# Cerebro.net
KiCad netlist of a schematic drawn in Altium Designer
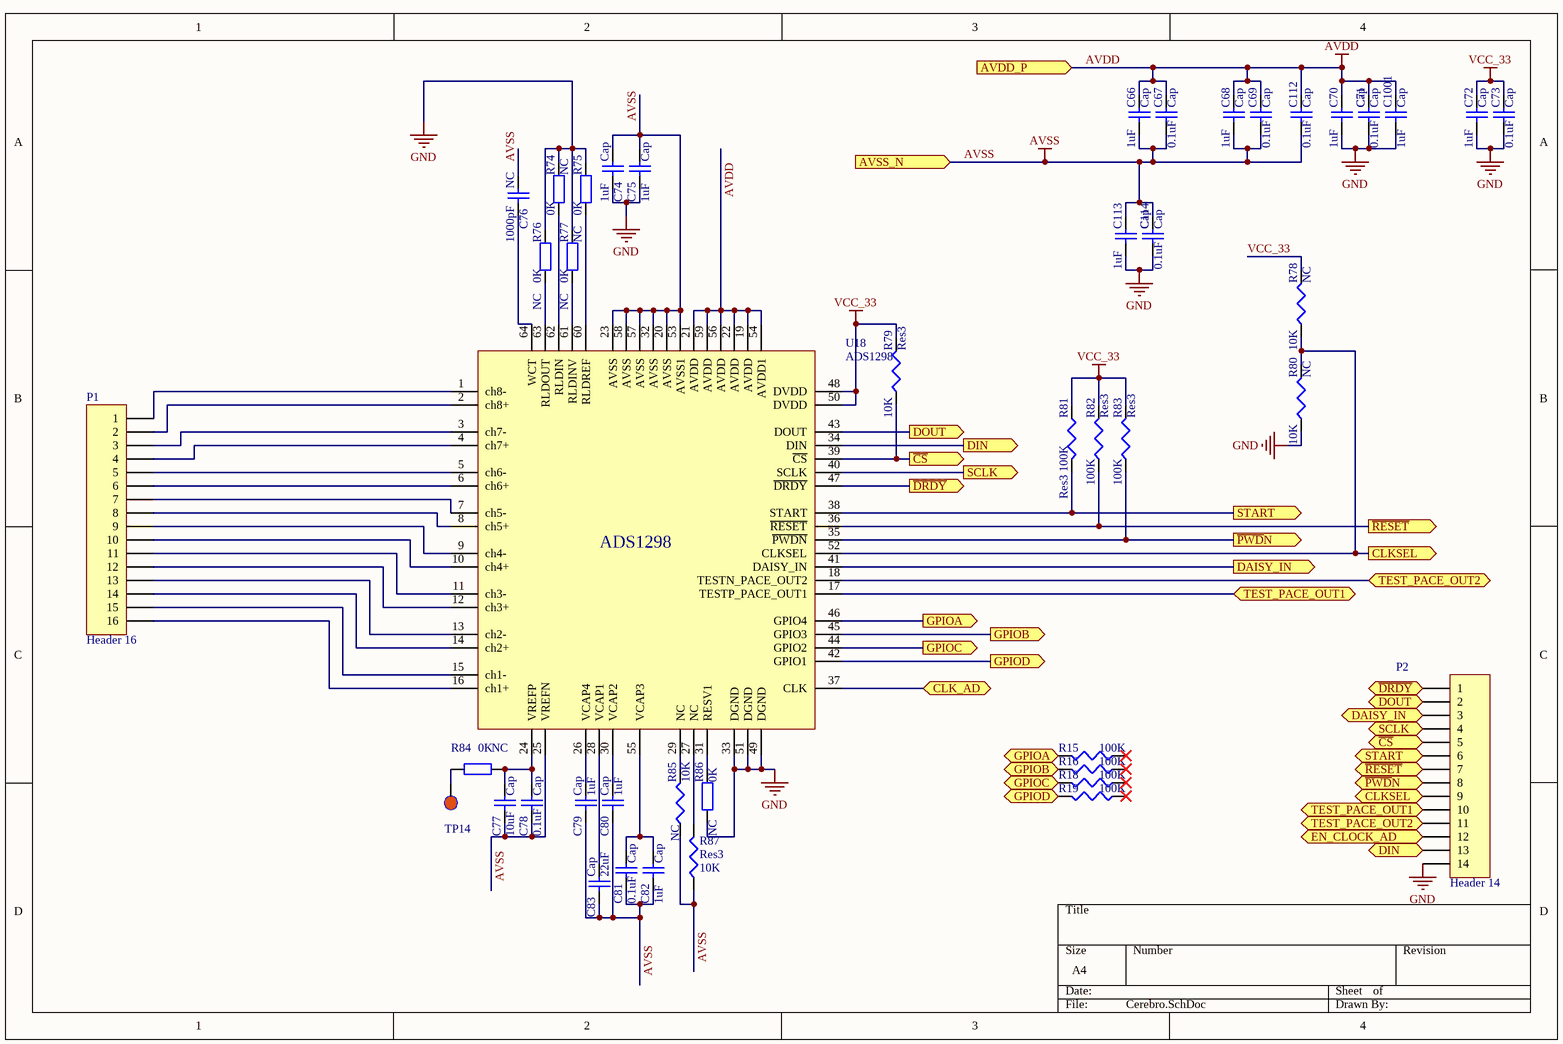
[diagram p0: Cerebro.SchDoc]

(export (version "E")
  (design (tool "Eeschema 10.0.6"))
  (components
    (comp (ref "C66")
      (value "Cap")
      (footprint "cap_0402_R - modified")
      (description "Capacitor")
      (fields (field (name "ALTIUM_VALUE") "1uF") (field (name "PUBLISHER") "Altium Limited"))
      (libsource (lib "Miscellaneous Devices") (part "Cap"))
    )
    (comp (ref "C67")
      (value "Cap")
      (footprint "cap_0402_R - modified")
      (description "Capacitor")
      (fields (field (name "ALTIUM_VALUE") "0.1uF") (field (name "PUBLISHER") "Altium Limited"))
      (libsource (lib "Miscellaneous Devices") (part "Cap"))
    )
    (comp (ref "C68")
      (value "Cap")
      (footprint "cap_0402_R - modified")
      (description "Capacitor")
      (fields (field (name "ALTIUM_VALUE") "1uF") (field (name "PUBLISHER") "Altium Limited"))
      (libsource (lib "Miscellaneous Devices") (part "Cap"))
    )
    (comp (ref "C69")
      (value "Cap")
      (footprint "cap_0402_R - modified")
      (description "Capacitor")
      (fields (field (name "ALTIUM_VALUE") "0.1uF") (field (name "PUBLISHER") "Altium Limited"))
      (libsource (lib "Miscellaneous Devices") (part "Cap"))
    )
    (comp (ref "C70")
      (value "Cap")
      (footprint "cap_0402_R - modified")
      (description "Capacitor")
      (fields (field (name "ALTIUM_VALUE") "1uF") (field (name "PUBLISHER") "Altium Limited"))
      (libsource (lib "Miscellaneous Devices") (part "Cap"))
    )
    (comp (ref "C71")
      (value "Cap")
      (footprint "cap_0402_R - modified")
      (description "Capacitor")
      (fields (field (name "ALTIUM_VALUE") "0.1uF") (field (name "PUBLISHER") "Altium Limited"))
      (libsource (lib "Miscellaneous Devices") (part "Cap"))
    )
    (comp (ref "C72")
      (value "Cap")
      (footprint "cap_0402_R - modified")
      (description "Capacitor")
      (fields (field (name "ALTIUM_VALUE") "1uF") (field (name "PUBLISHER") "Altium Limited"))
      (libsource (lib "Miscellaneous Devices") (part "Cap"))
    )
    (comp (ref "C73")
      (value "Cap")
      (footprint "cap_0402_R - modified")
      (description "Capacitor")
      (fields (field (name "ALTIUM_VALUE") "0.1uF") (field (name "PUBLISHER") "Altium Limited"))
      (libsource (lib "Miscellaneous Devices") (part "Cap"))
    )
    (comp (ref "C74")
      (value "Cap")
      (footprint "cap_0402_R - modified")
      (description "Capacitor")
      (fields (field (name "ALTIUM_VALUE") "1uF") (field (name "PUBLISHER") "Altium Limited"))
      (libsource (lib "Miscellaneous Devices") (part "Cap"))
    )
    (comp (ref "C75")
      (value "Cap")
      (footprint "cap_0402_R - modified")
      (description "Capacitor")
      (fields (field (name "ALTIUM_VALUE") "1uF") (field (name "PUBLISHER") "Altium Limited"))
      (libsource (lib "Miscellaneous Devices") (part "Cap"))
    )
    (comp (ref "C76")
      (value "NC")
      (footprint "cap_0402_R - modified")
      (description "Capacitor")
      (fields (field (name "ALTIUM_VALUE") "1000pF") (field (name "PUBLISHER") "Altium Limited"))
      (libsource (lib "Miscellaneous Devices") (part "Cap"))
    )
    (comp (ref "C77")
      (value "Cap")
      (footprint "cap_0402_R - modified")
      (description "Capacitor")
      (fields (field (name "ALTIUM_VALUE") "10uF") (field (name "PUBLISHER") "Altium Limited"))
      (libsource (lib "Miscellaneous Devices") (part "Cap"))
    )
    (comp (ref "C78")
      (value "Cap")
      (footprint "cap_0402_R - modified")
      (description "Capacitor")
      (fields (field (name "ALTIUM_VALUE") "0.1uF") (field (name "PUBLISHER") "Altium Limited"))
      (libsource (lib "Miscellaneous Devices") (part "Cap"))
    )
    (comp (ref "C79")
      (value "Cap")
      (footprint "cap_0402_R - modified")
      (description "Capacitor")
      (fields (field (name "ALTIUM_VALUE") "1uF") (field (name "PUBLISHER") "Altium Limited"))
      (libsource (lib "Miscellaneous Devices") (part "Cap"))
    )
    (comp (ref "C80")
      (value "Cap")
      (footprint "cap_0402_R - modified")
      (description "Capacitor")
      (fields (field (name "ALTIUM_VALUE") "1uF") (field (name "PUBLISHER") "Altium Limited"))
      (libsource (lib "Miscellaneous Devices") (part "Cap"))
    )
    (comp (ref "C81")
      (value "Cap")
      (footprint "cap_0402_R - modified")
      (description "Capacitor")
      (fields (field (name "ALTIUM_VALUE") "0.1uF") (field (name "PUBLISHER") "Altium Limited"))
      (libsource (lib "Miscellaneous Devices") (part "Cap"))
    )
    (comp (ref "C82")
      (value "Cap")
      (footprint "cap_0402_R - modified")
      (description "Capacitor")
      (fields (field (name "ALTIUM_VALUE") "1uF") (field (name "PUBLISHER") "Altium Limited"))
      (libsource (lib "Miscellaneous Devices") (part "Cap"))
    )
    (comp (ref "C83")
      (value "Cap")
      (footprint "cap_0402_R - modified")
      (description "Capacitor")
      (fields (field (name "ALTIUM_VALUE") "22uF") (field (name "PUBLISHER") "Altium Limited"))
      (libsource (lib "Miscellaneous Devices") (part "Cap"))
    )
    (comp (ref "C112")
      (value "Cap")
      (footprint "cap_0402_R - modified")
      (description "Capacitor")
      (fields (field (name "ALTIUM_VALUE") "0.1uF") (field (name "PUBLISHER") "Altium Limited"))
      (libsource (lib "Miscellaneous Devices") (part "Cap"))
    )
    (comp (ref "C113")
      (value "Cap")
      (footprint "cap_0402_R - modified")
      (description "Capacitor")
      (fields (field (name "ALTIUM_VALUE") "1uF") (field (name "PUBLISHER") "Altium Limited"))
      (libsource (lib "Miscellaneous Devices") (part "Cap"))
    )
    (comp (ref "C114")
      (value "Cap")
      (footprint "cap_0402_R - modified")
      (description "Capacitor")
      (fields (field (name "ALTIUM_VALUE") "0.1uF") (field (name "PUBLISHER") "Altium Limited"))
      (libsource (lib "Miscellaneous Devices") (part "Cap"))
    )
    (comp (ref "C1001")
      (value "Cap")
      (footprint "cap_0402_R - modified")
      (description "Capacitor")
      (fields (field (name "ALTIUM_VALUE") "1uF") (field (name "PUBLISHER") "Altium Limited"))
      (libsource (lib "Miscellaneous Devices") (part "Cap"))
    )
    (comp (ref "P1")
      (value "Header 16")
      (footprint "61301621121")
      (description "Header, 16-Pin")
      (fields (field (name "PUBLISHER") "Altium Limited"))
      (libsource (lib "Miscellaneous Connectors") (part "Header 16"))
    )
    (comp (ref "P2")
      (value "Header 14")
      (footprint "61301421121")
      (description "Header, 14-Pin")
      (fields (field (name "PUBLISHER") "Altium Limited"))
      (libsource (lib "Miscellaneous Connectors") (part "Header 14"))
    )
    (comp (ref "R15")
      (value "100K")
      (footprint "res_0402_R - modified")
      (description "Resistor")
      (fields (field (name "Comment") "Res3") (field (name "PUBLISHER") "Altium Limited"))
      (libsource (lib "Miscellaneous Devices") (part "Res3"))
    )
    (comp (ref "R16")
      (value "100K")
      (footprint "res_0402_R - modified")
      (description "Resistor")
      (fields (field (name "Comment") "Res3") (field (name "PUBLISHER") "Altium Limited"))
      (libsource (lib "Miscellaneous Devices") (part "Res3"))
    )
    (comp (ref "R18")
      (value "100K")
      (footprint "res_0402_R - modified")
      (description "Resistor")
      (fields (field (name "Comment") "Res3") (field (name "PUBLISHER") "Altium Limited"))
      (libsource (lib "Miscellaneous Devices") (part "Res3"))
    )
    (comp (ref "R19")
      (value "100K")
      (footprint "res_0402_R - modified")
      (description "Resistor")
      (fields (field (name "Comment") "Res3") (field (name "PUBLISHER") "Altium Limited"))
      (libsource (lib "Miscellaneous Devices") (part "Res3"))
    )
    (comp (ref "R74")
      (value "NC")
      (footprint "cap_0402_R - modified")
      (description "Resistor")
      (fields (field (name "ALTIUM_VALUE") "0K") (field (name "PUBLISHER") "Altium Limited"))
      (libsource (lib "Miscellaneous Devices") (part "Res2"))
    )
    (comp (ref "R75")
      (value "NC")
      (footprint "cap_0402_R - modified")
      (description "Resistor")
      (fields (field (name "ALTIUM_VALUE") "0K") (field (name "PUBLISHER") "Altium Limited"))
      (libsource (lib "Miscellaneous Devices") (part "Res2"))
    )
    (comp (ref "R76")
      (value "NC")
      (footprint "cap_0402_R - modified")
      (description "Resistor")
      (fields (field (name "ALTIUM_VALUE") "0K") (field (name "PUBLISHER") "Altium Limited"))
      (libsource (lib "Miscellaneous Devices") (part "Res2"))
    )
    (comp (ref "R77")
      (value "NC")
      (footprint "cap_0402_R - modified")
      (description "Resistor")
      (fields (field (name "ALTIUM_VALUE") "0K") (field (name "PUBLISHER") "Altium Limited"))
      (libsource (lib "Miscellaneous Devices") (part "Res2"))
    )
    (comp (ref "R78")
      (value "NC")
      (footprint "cap_0402_R - modified")
      (description "Resistor")
      (fields (field (name "ALTIUM_VALUE") "10K") (field (name "PUBLISHER") "Altium Limited"))
      (libsource (lib "Miscellaneous Devices") (part "Res3"))
    )
    (comp (ref "R79")
      (value "Res3")
      (footprint "res_0402_R - modified")
      (description "Resistor")
      (fields (field (name "ALTIUM_VALUE") "10K") (field (name "PUBLISHER") "Altium Limited"))
      (libsource (lib "Miscellaneous Devices") (part "Res3"))
    )
    (comp (ref "R80")
      (value "NC")
      (footprint "cap_0402_R - modified")
      (description "Resistor")
      (fields (field (name "ALTIUM_VALUE") "10K") (field (name "PUBLISHER") "Altium Limited"))
      (libsource (lib "Miscellaneous Devices") (part "Res3"))
    )
    (comp (ref "R81")
      (value "Res3")
      (footprint "res_0402_R - modified")
      (description "Resistor")
      (fields (field (name "ALTIUM_VALUE") "100K") (field (name "PUBLISHER") "Altium Limited"))
      (libsource (lib "Miscellaneous Devices") (part "Res3"))
    )
    (comp (ref "R82")
      (value "Res3")
      (footprint "res_0402_R - modified")
      (description "Resistor")
      (fields (field (name "ALTIUM_VALUE") "100K") (field (name "PUBLISHER") "Altium Limited"))
      (libsource (lib "Miscellaneous Devices") (part "Res3"))
    )
    (comp (ref "R83")
      (value "Res3")
      (footprint "res_0402_R - modified")
      (description "Resistor")
      (fields (field (name "ALTIUM_VALUE") "100K") (field (name "PUBLISHER") "Altium Limited"))
      (libsource (lib "Miscellaneous Devices") (part "Res3"))
    )
    (comp (ref "R84")
      (value "NC")
      (footprint "cap_0402_R - modified")
      (description "Resistor")
      (fields (field (name "ALTIUM_VALUE") "0K") (field (name "PUBLISHER") "Altium Limited"))
      (libsource (lib "") (part "Res2_1"))
    )
    (comp (ref "R85")
      (value "NC")
      (footprint "cap_0402_R - modified")
      (description "Resistor")
      (fields (field (name "ALTIUM_VALUE") "10K") (field (name "PUBLISHER") "Altium Limited"))
      (libsource (lib "Miscellaneous Devices") (part "Res3"))
    )
    (comp (ref "R86")
      (value "NC")
      (footprint "cap_0402_R - modified")
      (description "Resistor")
      (fields (field (name "ALTIUM_VALUE") "0K") (field (name "PUBLISHER") "Altium Limited"))
      (libsource (lib "Miscellaneous Devices") (part "Res2"))
    )
    (comp (ref "R87")
      (value "Res3")
      (footprint "res_0402_R - modified")
      (description "Resistor")
      (fields (field (name "ALTIUM_VALUE") "10K") (field (name "PUBLISHER") "Altium Limited"))
      (libsource (lib "Miscellaneous Devices") (part "Res3"))
    )
    (comp (ref "TP14")
      (value "1-PIN")
      (footprint "Testpt_055")
      (libsource (lib "Node_ADS_SchLib") (part "1-PIN"))
    )
    (comp (ref "U18")
      (value "ADS1298")
      (footprint "S-PQFP - G64 - ADS1298")
      (libsource (lib "Demo_Board_library_SCH") (part "ADS1298"))
    )
  )
  (nets
    (net (code "1") (name "/CLKSEL") (class "Default")
      (node (ref "P2") (pin "9") (pinfunction "9_9") (pintype "passive"))
      (node (ref "R78") (pin "1") (pinfunction "1_1") (pintype "passive"))
      (node (ref "R80") (pin "2") (pinfunction "2_2") (pintype "passive"))
      (node (ref "U18") (pin "52") (pinfunction "CLKSEL_52") (pintype "passive"))
    )
    (net (code "2") (name "/CLK_AD") (class "Default")
      (node (ref "U18") (pin "37") (pinfunction "CLK_37") (pintype "passive"))
    )
    (net (code "3") (name "/DAISY_IN") (class "Default")
      (node (ref "P2") (pin "3") (pinfunction "3_3") (pintype "passive"))
      (node (ref "U18") (pin "41") (pinfunction "DAISY_IN_41") (pintype "passive"))
    )
    (net (code "4") (name "/DIN") (class "Default")
      (node (ref "P2") (pin "13") (pinfunction "13_13") (pintype "passive"))
      (node (ref "U18") (pin "34") (pinfunction "DIN_34") (pintype "passive"))
    )
    (net (code "5") (name "/DOUT") (class "Default")
      (node (ref "P2") (pin "2") (pinfunction "2_2") (pintype "passive"))
      (node (ref "U18") (pin "43") (pinfunction "DOUT_43") (pintype "passive"))
    )
    (net (code "6") (name "/EN_CLOCK_AD") (class "Default")
      (node (ref "P2") (pin "12") (pinfunction "12_12") (pintype "passive"))
    )
    (net (code "7") (name "/GPIOA") (class "Default")
      (node (ref "R15") (pin "2") (pinfunction "2_2") (pintype "passive"))
      (node (ref "U18") (pin "46") (pinfunction "GPIO4_46") (pintype "passive"))
    )
    (net (code "8") (name "/GPIOB") (class "Default")
      (node (ref "R16") (pin "2") (pinfunction "2_2") (pintype "passive"))
      (node (ref "U18") (pin "45") (pinfunction "GPIO3_45") (pintype "passive"))
    )
    (net (code "9") (name "/GPIOC") (class "Default")
      (node (ref "R18") (pin "2") (pinfunction "2_2") (pintype "passive"))
      (node (ref "U18") (pin "44") (pinfunction "GPIO2_44") (pintype "passive"))
    )
    (net (code "10") (name "/GPIOD") (class "Default")
      (node (ref "R19") (pin "2") (pinfunction "2_2") (pintype "passive"))
      (node (ref "U18") (pin "42") (pinfunction "GPIO1_42") (pintype "passive"))
    )
    (net (code "11") (name "/SCLK") (class "Default")
      (node (ref "P2") (pin "4") (pinfunction "4_4") (pintype "passive"))
      (node (ref "U18") (pin "40") (pinfunction "SCLK_40") (pintype "passive"))
    )
    (net (code "12") (name "/START") (class "Default")
      (node (ref "P2") (pin "6") (pinfunction "6_6") (pintype "passive"))
      (node (ref "R81") (pin "2") (pinfunction "2_2") (pintype "passive"))
      (node (ref "U18") (pin "38") (pinfunction "START_38") (pintype "passive"))
    )
    (net (code "13") (name "/TEST_PACE_OUT1") (class "Default")
      (node (ref "P2") (pin "10") (pinfunction "10_10") (pintype "passive"))
      (node (ref "U18") (pin "17") (pinfunction "TESTP_PACE_OUT1_17") (pintype "passive"))
    )
    (net (code "14") (name "/TEST_PACE_OUT2") (class "Default")
      (node (ref "P2") (pin "11") (pinfunction "11_11") (pintype "passive"))
      (node (ref "U18") (pin "18") (pinfunction "TESTN_PACE_OUT2_18") (pintype "passive"))
    )
    (net (code "15") (name "/~{CS}") (class "Default")
      (node (ref "P2") (pin "5") (pinfunction "5_5") (pintype "passive"))
      (node (ref "R79") (pin "1") (pinfunction "1_1") (pintype "passive"))
      (node (ref "U18") (pin "39") (pinfunction "~{CS}_39") (pintype "passive"))
    )
    (net (code "16") (name "/~{DRDY}") (class "Default")
      (node (ref "P2") (pin "1") (pinfunction "1_1") (pintype "passive"))
      (node (ref "U18") (pin "47") (pinfunction "~{DRDY}_47") (pintype "passive"))
    )
    (net (code "17") (name "/~{PWD}N") (class "Default")
      (node (ref "P2") (pin "8") (pinfunction "8_8") (pintype "passive"))
      (node (ref "R83") (pin "1") (pinfunction "1_1") (pintype "passive"))
      (node (ref "U18") (pin "35") (pinfunction "~{PWDN}_35") (pintype "passive"))
    )
    (net (code "18") (name "/~{RESET}") (class "Default")
      (node (ref "P2") (pin "7") (pinfunction "7_7") (pintype "passive"))
      (node (ref "R82") (pin "1") (pinfunction "1_1") (pintype "passive"))
      (node (ref "U18") (pin "36") (pinfunction "~{RESET}_36") (pintype "passive"))
    )
    (net (code "19") (name "AVDD") (class "Default")
      (node (ref "C1001") (pin "2") (pinfunction "2_2") (pintype "passive"))
      (node (ref "C112") (pin "2") (pinfunction "2_2") (pintype "passive"))
      (node (ref "C66") (pin "2") (pinfunction "2_2") (pintype "passive"))
      (node (ref "C67") (pin "2") (pinfunction "2_2") (pintype "passive"))
      (node (ref "C68") (pin "2") (pinfunction "2_2") (pintype "passive"))
      (node (ref "C69") (pin "2") (pinfunction "2_2") (pintype "passive"))
      (node (ref "C70") (pin "2") (pinfunction "2_2") (pintype "passive"))
      (node (ref "C71") (pin "2") (pinfunction "2_2") (pintype "passive"))
      (node (ref "U18") (pin "19") (pinfunction "AVDD_19") (pintype "passive"))
      (node (ref "U18") (pin "21") (pinfunction "AVDD_21") (pintype "passive"))
      (node (ref "U18") (pin "22") (pinfunction "AVDD_22") (pintype "passive"))
      (node (ref "U18") (pin "54") (pinfunction "AVDD1_54") (pintype "passive"))
      (node (ref "U18") (pin "56") (pinfunction "AVDD_56") (pintype "passive"))
      (node (ref "U18") (pin "59") (pinfunction "AVDD_59") (pintype "passive"))
    )
    (net (code "20") (name "AVSS") (class "Default")
      (node (ref "C112") (pin "1") (pinfunction "1_1") (pintype "passive"))
      (node (ref "C113") (pin "2") (pinfunction "2_2") (pintype "passive"))
      (node (ref "C114") (pin "2") (pinfunction "2_2") (pintype "passive"))
      (node (ref "C66") (pin "1") (pinfunction "1_1") (pintype "passive"))
      (node (ref "C67") (pin "1") (pinfunction "1_1") (pintype "passive"))
      (node (ref "C68") (pin "1") (pinfunction "1_1") (pintype "passive"))
      (node (ref "C69") (pin "1") (pinfunction "1_1") (pintype "passive"))
      (node (ref "C74") (pin "1") (pinfunction "1_1") (pintype "passive"))
      (node (ref "C75") (pin "1") (pinfunction "1_1") (pintype "passive"))
      (node (ref "C76") (pin "1") (pinfunction "1_1") (pintype "passive"))
      (node (ref "C77") (pin "1") (pinfunction "1_1") (pintype "passive"))
      (node (ref "C78") (pin "1") (pinfunction "1_1") (pintype "passive"))
      (node (ref "C79") (pin "1") (pinfunction "1_1") (pintype "passive"))
      (node (ref "C80") (pin "1") (pinfunction "1_1") (pintype "passive"))
      (node (ref "C81") (pin "1") (pinfunction "1_1") (pintype "passive"))
      (node (ref "C82") (pin "1") (pinfunction "1_1") (pintype "passive"))
      (node (ref "C83") (pin "1") (pinfunction "1_1") (pintype "passive"))
      (node (ref "R85") (pin "1") (pinfunction "1_1") (pintype "passive"))
      (node (ref "R87") (pin "1") (pinfunction "1_1") (pintype "passive"))
      (node (ref "U18") (pin "20") (pinfunction "AVSS_20") (pintype "passive"))
      (node (ref "U18") (pin "23") (pinfunction "AVSS_23") (pintype "passive"))
      (node (ref "U18") (pin "25") (pinfunction "VREFN_25") (pintype "passive"))
      (node (ref "U18") (pin "32") (pinfunction "AVSS_32") (pintype "passive"))
      (node (ref "U18") (pin "53") (pinfunction "AVSS1_53") (pintype "passive"))
      (node (ref "U18") (pin "57") (pinfunction "AVSS_57") (pintype "passive"))
      (node (ref "U18") (pin "58") (pinfunction "AVSS_58") (pintype "passive"))
    )
    (net (code "21") (name "GND") (class "Default")
      (node (ref "C1001") (pin "1") (pinfunction "1_1") (pintype "passive"))
      (node (ref "C113") (pin "1") (pinfunction "1_1") (pintype "passive"))
      (node (ref "C114") (pin "1") (pinfunction "1_1") (pintype "passive"))
      (node (ref "C70") (pin "1") (pinfunction "1_1") (pintype "passive"))
      (node (ref "C71") (pin "1") (pinfunction "1_1") (pintype "passive"))
      (node (ref "C72") (pin "1") (pinfunction "1_1") (pintype "passive"))
      (node (ref "C73") (pin "1") (pinfunction "1_1") (pintype "passive"))
      (node (ref "C74") (pin "2") (pinfunction "2_2") (pintype "passive"))
      (node (ref "C75") (pin "2") (pinfunction "2_2") (pintype "passive"))
      (node (ref "P2") (pin "14") (pinfunction "14_14") (pintype "passive"))
      (node (ref "R74") (pin "1") (pinfunction "1_1") (pintype "passive"))
      (node (ref "R75") (pin "1") (pinfunction "1_1") (pintype "passive"))
      (node (ref "R76") (pin "1") (pinfunction "1_1") (pintype "passive"))
      (node (ref "R77") (pin "1") (pinfunction "1_1") (pintype "passive"))
      (node (ref "R80") (pin "1") (pinfunction "1_1") (pintype "passive"))
      (node (ref "R86") (pin "2") (pinfunction "2_2") (pintype "passive"))
      (node (ref "U18") (pin "33") (pinfunction "DGND_33") (pintype "passive"))
      (node (ref "U18") (pin "49") (pinfunction "DGND_49") (pintype "passive"))
      (node (ref "U18") (pin "51") (pinfunction "DGND_51") (pintype "passive"))
    )
    (net (code "22") (name "Net-(R84-Pad1)") (class "Default")
      (node (ref "R84") (pin "1") (pinfunction "1_1") (pintype "passive"))
      (node (ref "TP14") (pin "1") (pinfunction "1_1") (pintype "passive"))
    )
    (net (code "23") (name "Net-(R85-Pad2)") (class "Default")
      (node (ref "R85") (pin "2") (pinfunction "2_2") (pintype "passive"))
      (node (ref "U18") (pin "29") (pinfunction "NC_29") (pintype "passive"))
    )
    (net (code "24") (name "Net-(R87-Pad2)") (class "Default")
      (node (ref "R87") (pin "2") (pinfunction "2_2") (pintype "passive"))
      (node (ref "U18") (pin "27") (pinfunction "NC_27") (pintype "passive"))
    )
    (net (code "25") (name "Net-(U18-RESV1)") (class "Default")
      (node (ref "R86") (pin "1") (pinfunction "1_1") (pintype "passive"))
      (node (ref "U18") (pin "31") (pinfunction "RESV1_31") (pintype "passive"))
    )
    (net (code "26") (name "Net-(U18-RLDIN)") (class "Default")
      (node (ref "R74") (pin "2") (pinfunction "2_2") (pintype "passive"))
      (node (ref "U18") (pin "62") (pinfunction "RLDIN_62") (pintype "passive"))
    )
    (net (code "27") (name "Net-(U18-RLDINV)") (class "Default")
      (node (ref "R77") (pin "2") (pinfunction "2_2") (pintype "passive"))
      (node (ref "U18") (pin "61") (pinfunction "RLDINV_61") (pintype "passive"))
    )
    (net (code "28") (name "Net-(U18-RLDOUT)") (class "Default")
      (node (ref "R76") (pin "2") (pinfunction "2_2") (pintype "passive"))
      (node (ref "U18") (pin "63") (pinfunction "RLDOUT_63") (pintype "passive"))
    )
    (net (code "29") (name "Net-(U18-RLDREF)") (class "Default")
      (node (ref "R75") (pin "2") (pinfunction "2_2") (pintype "passive"))
      (node (ref "U18") (pin "60") (pinfunction "RLDREF_60") (pintype "passive"))
    )
    (net (code "30") (name "Net-(U18-VCAP1)") (class "Default")
      (node (ref "C83") (pin "2") (pinfunction "2_2") (pintype "passive"))
      (node (ref "U18") (pin "28") (pinfunction "VCAP1_28") (pintype "passive"))
    )
    (net (code "31") (name "Net-(U18-VCAP2)") (class "Default")
      (node (ref "C80") (pin "2") (pinfunction "2_2") (pintype "passive"))
      (node (ref "U18") (pin "30") (pinfunction "VCAP2_30") (pintype "passive"))
    )
    (net (code "32") (name "Net-(U18-VCAP3)") (class "Default")
      (node (ref "C81") (pin "2") (pinfunction "2_2") (pintype "passive"))
      (node (ref "C82") (pin "2") (pinfunction "2_2") (pintype "passive"))
      (node (ref "U18") (pin "55") (pinfunction "VCAP3_55") (pintype "passive"))
    )
    (net (code "33") (name "Net-(U18-VCAP4)") (class "Default")
      (node (ref "C79") (pin "2") (pinfunction "2_2") (pintype "passive"))
      (node (ref "U18") (pin "26") (pinfunction "VCAP4_26") (pintype "passive"))
    )
    (net (code "34") (name "Net-(U18-VREFP)") (class "Default")
      (node (ref "C77") (pin "2") (pinfunction "2_2") (pintype "passive"))
      (node (ref "C78") (pin "2") (pinfunction "2_2") (pintype "passive"))
      (node (ref "R84") (pin "2") (pinfunction "2_2") (pintype "passive"))
      (node (ref "U18") (pin "24") (pinfunction "VREFP_24") (pintype "passive"))
    )
    (net (code "35") (name "Net-(U18-WCT)") (class "Default")
      (node (ref "C76") (pin "2") (pinfunction "2_2") (pintype "passive"))
      (node (ref "U18") (pin "64") (pinfunction "WCT_64") (pintype "passive"))
    )
    (net (code "36") (name "Net-(U18-ch1+)") (class "Default")
      (node (ref "P1") (pin "16") (pinfunction "16_16") (pintype "passive"))
      (node (ref "U18") (pin "16") (pinfunction "ch1+_16") (pintype "passive"))
    )
    (net (code "37") (name "Net-(U18-ch1-)") (class "Default")
      (node (ref "P1") (pin "15") (pinfunction "15_15") (pintype "passive"))
      (node (ref "U18") (pin "15") (pinfunction "ch1-_15") (pintype "passive"))
    )
    (net (code "38") (name "Net-(U18-ch2+)") (class "Default")
      (node (ref "P1") (pin "14") (pinfunction "14_14") (pintype "passive"))
      (node (ref "U18") (pin "14") (pinfunction "ch2+_14") (pintype "passive"))
    )
    (net (code "39") (name "Net-(U18-ch2-)") (class "Default")
      (node (ref "P1") (pin "13") (pinfunction "13_13") (pintype "passive"))
      (node (ref "U18") (pin "13") (pinfunction "ch2-_13") (pintype "passive"))
    )
    (net (code "40") (name "Net-(U18-ch3+)") (class "Default")
      (node (ref "P1") (pin "12") (pinfunction "12_12") (pintype "passive"))
      (node (ref "U18") (pin "12") (pinfunction "ch3+_12") (pintype "passive"))
    )
    (net (code "41") (name "Net-(U18-ch3-)") (class "Default")
      (node (ref "P1") (pin "11") (pinfunction "11_11") (pintype "passive"))
      (node (ref "U18") (pin "11") (pinfunction "ch3-_11") (pintype "passive"))
    )
    (net (code "42") (name "Net-(U18-ch4+)") (class "Default")
      (node (ref "P1") (pin "10") (pinfunction "10_10") (pintype "passive"))
      (node (ref "U18") (pin "10") (pinfunction "ch4+_10") (pintype "passive"))
    )
    (net (code "43") (name "Net-(U18-ch4-)") (class "Default")
      (node (ref "P1") (pin "9") (pinfunction "9_9") (pintype "passive"))
      (node (ref "U18") (pin "9") (pinfunction "ch4-_9") (pintype "passive"))
    )
    (net (code "44") (name "Net-(U18-ch5+)") (class "Default")
      (node (ref "P1") (pin "8") (pinfunction "8_8") (pintype "passive"))
      (node (ref "U18") (pin "8") (pinfunction "ch5+_8") (pintype "passive"))
    )
    (net (code "45") (name "Net-(U18-ch5-)") (class "Default")
      (node (ref "P1") (pin "7") (pinfunction "7_7") (pintype "passive"))
      (node (ref "U18") (pin "7") (pinfunction "ch5-_7") (pintype "passive"))
    )
    (net (code "46") (name "Net-(U18-ch6+)") (class "Default")
      (node (ref "P1") (pin "6") (pinfunction "6_6") (pintype "passive"))
      (node (ref "U18") (pin "6") (pinfunction "ch6+_6") (pintype "passive"))
    )
    (net (code "47") (name "Net-(U18-ch6-)") (class "Default")
      (node (ref "P1") (pin "5") (pinfunction "5_5") (pintype "passive"))
      (node (ref "U18") (pin "5") (pinfunction "ch6-_5") (pintype "passive"))
    )
    (net (code "48") (name "Net-(U18-ch7+)") (class "Default")
      (node (ref "P1") (pin "4") (pinfunction "4_4") (pintype "passive"))
      (node (ref "U18") (pin "4") (pinfunction "ch7+_4") (pintype "passive"))
    )
    (net (code "49") (name "Net-(U18-ch7-)") (class "Default")
      (node (ref "P1") (pin "3") (pinfunction "3_3") (pintype "passive"))
      (node (ref "U18") (pin "3") (pinfunction "ch7-_3") (pintype "passive"))
    )
    (net (code "50") (name "Net-(U18-ch8+)") (class "Default")
      (node (ref "P1") (pin "2") (pinfunction "2_2") (pintype "passive"))
      (node (ref "U18") (pin "2") (pinfunction "ch8+_2") (pintype "passive"))
    )
    (net (code "51") (name "Net-(U18-ch8-)") (class "Default")
      (node (ref "P1") (pin "1") (pinfunction "1_1") (pintype "passive"))
      (node (ref "U18") (pin "1") (pinfunction "ch8-_1") (pintype "passive"))
    )
    (net (code "52") (name "VCC_33") (class "Default")
      (node (ref "C72") (pin "2") (pinfunction "2_2") (pintype "passive"))
      (node (ref "C73") (pin "2") (pinfunction "2_2") (pintype "passive"))
      (node (ref "R78") (pin "2") (pinfunction "2_2") (pintype "passive"))
      (node (ref "R79") (pin "2") (pinfunction "2_2") (pintype "passive"))
      (node (ref "R81") (pin "1") (pinfunction "1_1") (pintype "passive"))
      (node (ref "R82") (pin "2") (pinfunction "2_2") (pintype "passive"))
      (node (ref "R83") (pin "2") (pinfunction "2_2") (pintype "passive"))
      (node (ref "U18") (pin "48") (pinfunction "DVDD_48") (pintype "passive"))
      (node (ref "U18") (pin "50") (pinfunction "DVDD_50") (pintype "passive"))
    )
    (net (code "53") (name "unconnected-(R15-Pad1)") (class "Default")
      (node (ref "R15") (pin "1") (pinfunction "1_1") (pintype "passive+no_connect"))
    )
    (net (code "54") (name "unconnected-(R16-Pad1)") (class "Default")
      (node (ref "R16") (pin "1") (pinfunction "1_1") (pintype "passive+no_connect"))
    )
    (net (code "55") (name "unconnected-(R18-Pad1)") (class "Default")
      (node (ref "R18") (pin "1") (pinfunction "1_1") (pintype "passive+no_connect"))
    )
    (net (code "56") (name "unconnected-(R19-Pad1)") (class "Default")
      (node (ref "R19") (pin "1") (pinfunction "1_1") (pintype "passive+no_connect"))
    )
  )
)
